# Power_Stage.net
KiCad netlist of a schematic drawn in Altium Designer
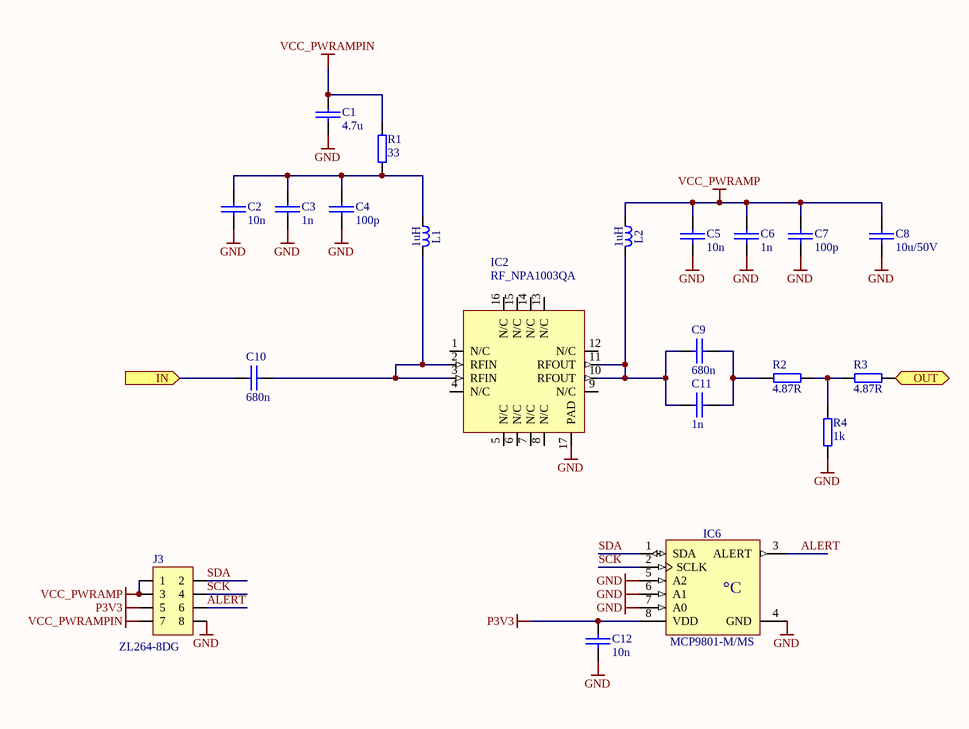
[diagram p0: Power_Stage.SchDoc]

(export (version "E")
  (design (tool "Eeschema 10.0.6"))
  (components
    (comp (ref "C1")
      (value "4.7u")
      (footprint "0603C")
      (description "Capacitor SMD")
      (fields (field (name "PART") "GRM21BR71C475KE51L"))
      (libsource (lib "LIBRARY_SCH") (part "CAP_SMD_0603"))
    )
    (comp (ref "C2")
      (value "10n")
      (footprint "0603C")
      (description "Capacitor SMD")
      (fields (field (name "PART") "GRM1885C1H103JA01D"))
      (libsource (lib "LIBRARY_SCH") (part "CAP_SMD_0603"))
    )
    (comp (ref "C3")
      (value "1n")
      (footprint "0603C")
      (description "Capacitor SMD")
      (fields (field (name "PART") "GRM1885C1H102JA01D"))
      (libsource (lib "LIBRARY_SCH") (part "CAP_SMD_0603"))
    )
    (comp (ref "C4")
      (value "100p")
      (footprint "0603C")
      (description "Capacitor SMD")
      (fields (field (name "PART") "C1608NP01H101J080AA"))
      (libsource (lib "LIBRARY_SCH") (part "CAP_SMD_0603"))
    )
    (comp (ref "C5")
      (value "10n")
      (footprint "0603C")
      (description "Capacitor SMD")
      (fields (field (name "PART") "GRM1885C1H103JA01D"))
      (libsource (lib "LIBRARY_SCH") (part "CAP_SMD_0603"))
    )
    (comp (ref "C6")
      (value "1n")
      (footprint "0603C")
      (description "Capacitor SMD")
      (fields (field (name "PART") "GRM1885C1H102JA01D"))
      (libsource (lib "LIBRARY_SCH") (part "CAP_SMD_0603"))
    )
    (comp (ref "C7")
      (value "100p")
      (footprint "0603C")
      (description "Capacitor SMD")
      (fields (field (name "PART") "C1608NP01H101J080AA"))
      (libsource (lib "LIBRARY_SCH") (part "CAP_SMD_0603"))
    )
    (comp (ref "C8")
      (value "10u/50V")
      (footprint "0805C")
      (description "Capacitor SMD")
      (fields (field (name "PART") "GRM32ER71H106KA12L"))
      (libsource (lib "LIBRARY_SCH") (part "CAP_SMD_0805"))
    )
    (comp (ref "C9")
      (value "680n")
      (footprint "0603C")
      (description "Capacitor SMD")
      (fields (field (name "PART") "GRM1555C1H681GA01"))
      (libsource (lib "LIBRARY_SCH") (part "CAP_SMD_0603"))
    )
    (comp (ref "C10")
      (value "680n")
      (footprint "0603C")
      (description "Capacitor SMD")
      (fields (field (name "PART") "GRM1555C1H681GA01"))
      (libsource (lib "LIBRARY_SCH") (part "CAP_SMD_0603"))
    )
    (comp (ref "C11")
      (value "1n")
      (footprint "0603C")
      (description "Capacitor SMD")
      (fields (field (name "PART") "GRM1885C1H102JA01D"))
      (libsource (lib "LIBRARY_SCH") (part "CAP_SMD_0603"))
    )
    (comp (ref "C12")
      (value "10n")
      (footprint "0603C")
      (description "Capacitor SMD")
      (libsource (lib "LIBRARY_SCH") (part "CAP_SMD_0603"))
    )
    (comp (ref "IC2")
      (value "RF_NPA1003QA")
      (footprint "QFN65P400X400X80_HS-17N")
      (libsource (lib "LIBRARY_SCH") (part "RF_NPA1003QA"))
    )
    (comp (ref "IC6")
      (value "MCP9801-M/MS")
      (footprint "SOP65P490X110-8N")
      (description "2-Wire High-Accuracy Temperature Sensor")
      (fields (field (name "MANUFACTURER") "MICROCHIP TECHNOLOGIY") (field (name "AUTHOR") "CERN DEM JLC"))
      (libsource (lib "ICs And Semiconductors") (part "MCP9801-M/MS"))
    )
    (comp (ref "J3")
      (value "ZL264-8DG")
      (footprint "ZL264-8DG")
      (description "2.54mm pitch connector")
      (libsource (lib "LIBRARY_SCH") (part "CON_2X4 2.54 SMT FEM"))
    )
    (comp (ref "L1")
      (value "1uH")
      (footprint "INDP2520X18L")
      (fields (field (name "PART") "LQW2UAS1R0J00L") (field (name "AUTHOR") "GK"))
      (libsource (lib "LIBRARY_SCH") (part "L_1008_100u"))
    )
    (comp (ref "L2")
      (value "1uH")
      (footprint "INDP2520X18L")
      (description "100uH, 60mA, 21R")
      (fields (field (name "PART") "1008LS-102XJLB") (field (name "AUTHOR") "GK"))
      (libsource (lib "LIBRARY_SCH") (part "L_1008_100u"))
    )
    (comp (ref "R1")
      (value "33")
      (footprint "0603R")
      (description "SMD Resistor")
      (fields (field (name "PART") "CR0603-FX-33R0ELF"))
      (libsource (lib "LIBRARY_SCH") (part "RES_0603"))
    )
    (comp (ref "R2")
      (value "4.87R")
      (footprint "0603R")
      (description "SMD Resistor")
      (fields (field (name "PART") "CPF0603B4R87E1"))
      (libsource (lib "LIBRARY_SCH") (part "RES_0603"))
    )
    (comp (ref "R3")
      (value "4.87R")
      (footprint "0603R")
      (description "SMD Resistor")
      (fields (field (name "PART") "CPF0603B4R87E1"))
      (libsource (lib "LIBRARY_SCH") (part "RES_0603"))
    )
    (comp (ref "R4")
      (value "1k")
      (footprint "0603R")
      (description "SMD Resistor")
      (fields (field (name "PART") "RP73PF1J1K0BTDF"))
      (libsource (lib "LIBRARY_SCH") (part "RES_0603"))
    )
  )
  (nets
    (net (code "1") (name "/ALERT") (class "Default")
      (node (ref "IC6") (pin "3") (pinfunction "ALERT_3") (pintype "output"))
      (node (ref "J3") (pin "6") (pinfunction "6_6") (pintype "passive"))
    )
    (net (code "2") (name "/IN") (class "Default")
      (node (ref "C10") (pin "1") (pinfunction "1_1") (pintype "passive"))
    )
    (net (code "3") (name "/OUT") (class "Default")
      (node (ref "R3") (pin "2") (pinfunction "2_2") (pintype "passive"))
    )
    (net (code "4") (name "/SCK") (class "Default")
      (node (ref "IC6") (pin "2") (pinfunction "SCLK_2") (pintype "input"))
      (node (ref "J3") (pin "4") (pinfunction "4_4") (pintype "passive"))
    )
    (net (code "5") (name "/SDA") (class "Default")
      (node (ref "IC6") (pin "1") (pinfunction "SDA_1") (pintype "bidirectional"))
      (node (ref "J3") (pin "2") (pinfunction "2_2") (pintype "passive"))
    )
    (net (code "6") (name "GND") (class "Default")
      (node (ref "C1") (pin "2") (pinfunction "2_2") (pintype "passive"))
      (node (ref "C12") (pin "1") (pinfunction "1_1") (pintype "passive"))
      (node (ref "C2") (pin "2") (pinfunction "2_2") (pintype "passive"))
      (node (ref "C3") (pin "2") (pinfunction "2_2") (pintype "passive"))
      (node (ref "C4") (pin "2") (pinfunction "2_2") (pintype "passive"))
      (node (ref "C5") (pin "2") (pinfunction "2_2") (pintype "passive"))
      (node (ref "C6") (pin "2") (pinfunction "2_2") (pintype "passive"))
      (node (ref "C7") (pin "2") (pinfunction "2_2") (pintype "passive"))
      (node (ref "C8") (pin "2") (pinfunction "2_2") (pintype "passive"))
      (node (ref "IC2") (pin "17") (pinfunction "PAD_17") (pintype "passive"))
      (node (ref "IC6") (pin "4") (pinfunction "GND_4") (pintype "power_in"))
      (node (ref "IC6") (pin "5") (pinfunction "A2_5") (pintype "input"))
      (node (ref "IC6") (pin "6") (pinfunction "A1_6") (pintype "input"))
      (node (ref "IC6") (pin "7") (pinfunction "A0_7") (pintype "input"))
      (node (ref "J3") (pin "8") (pinfunction "8_8") (pintype "passive"))
      (node (ref "R4") (pin "1") (pinfunction "1_1") (pintype "passive"))
    )
    (net (code "7") (name "Net-(C2-Pad1)") (class "Default")
      (node (ref "C2") (pin "1") (pinfunction "1_1") (pintype "passive"))
      (node (ref "C3") (pin "1") (pinfunction "1_1") (pintype "passive"))
      (node (ref "C4") (pin "1") (pinfunction "1_1") (pintype "passive"))
      (node (ref "L1") (pin "1") (pinfunction "1_1") (pintype "passive"))
      (node (ref "R1") (pin "1") (pinfunction "1_1") (pintype "passive"))
    )
    (net (code "8") (name "Net-(C10-Pad2)") (class "Default")
      (node (ref "C10") (pin "2") (pinfunction "2_2") (pintype "passive"))
      (node (ref "IC2") (pin "2") (pinfunction "RFIN_2") (pintype "input"))
      (node (ref "IC2") (pin "3") (pinfunction "RFIN_3") (pintype "input"))
      (node (ref "L1") (pin "2") (pinfunction "2_2") (pintype "passive"))
    )
    (net (code "9") (name "Net-(C11-Pad1)") (class "Default")
      (node (ref "C11") (pin "1") (pinfunction "1_1") (pintype "passive"))
      (node (ref "C9") (pin "1") (pinfunction "1_1") (pintype "passive"))
      (node (ref "IC2") (pin "10") (pinfunction "RFOUT_10") (pintype "output"))
      (node (ref "IC2") (pin "11") (pinfunction "RFOUT_11") (pintype "output"))
      (node (ref "L2") (pin "2") (pinfunction "2_2") (pintype "passive"))
    )
    (net (code "10") (name "Net-(C11-Pad2)") (class "Default")
      (node (ref "C11") (pin "2") (pinfunction "2_2") (pintype "passive"))
      (node (ref "C9") (pin "2") (pinfunction "2_2") (pintype "passive"))
      (node (ref "R2") (pin "1") (pinfunction "1_1") (pintype "passive"))
    )
    (net (code "11") (name "Net-(R2-Pad2)") (class "Default")
      (node (ref "R2") (pin "2") (pinfunction "2_2") (pintype "passive"))
      (node (ref "R3") (pin "1") (pinfunction "1_1") (pintype "passive"))
      (node (ref "R4") (pin "2") (pinfunction "2_2") (pintype "passive"))
    )
    (net (code "12") (name "P3V3") (class "Default")
      (node (ref "C12") (pin "2") (pinfunction "2_2") (pintype "passive"))
      (node (ref "IC6") (pin "8") (pinfunction "VDD_8") (pintype "power_in"))
      (node (ref "J3") (pin "5") (pinfunction "5_5") (pintype "passive"))
    )
    (net (code "13") (name "VCC_PWRAMP") (class "Default")
      (node (ref "C5") (pin "1") (pinfunction "1_1") (pintype "passive"))
      (node (ref "C6") (pin "1") (pinfunction "1_1") (pintype "passive"))
      (node (ref "C7") (pin "1") (pinfunction "1_1") (pintype "passive"))
      (node (ref "C8") (pin "1") (pinfunction "1_1") (pintype "passive"))
      (node (ref "J3") (pin "1") (pinfunction "1_1") (pintype "passive"))
      (node (ref "J3") (pin "3") (pinfunction "3_3") (pintype "passive"))
      (node (ref "L2") (pin "1") (pinfunction "1_1") (pintype "passive"))
    )
    (net (code "14") (name "VCC_PWRAMPIN") (class "Default")
      (node (ref "C1") (pin "1") (pinfunction "1_1") (pintype "passive"))
      (node (ref "J3") (pin "7") (pinfunction "7_7") (pintype "passive"))
      (node (ref "R1") (pin "2") (pinfunction "2_2") (pintype "passive"))
    )
    (net (code "15") (name "unconnected-(IC2-N{slash}C-Pad1)") (class "Default")
      (node (ref "IC2") (pin "1") (pinfunction "N/C_1") (pintype "passive"))
    )
    (net (code "16") (name "unconnected-(IC2-N{slash}C-Pad4)") (class "Default")
      (node (ref "IC2") (pin "4") (pinfunction "N/C_4") (pintype "passive"))
    )
    (net (code "17") (name "unconnected-(IC2-N{slash}C-Pad5)") (class "Default")
      (node (ref "IC2") (pin "5") (pinfunction "N/C_5") (pintype "passive"))
    )
    (net (code "18") (name "unconnected-(IC2-N{slash}C-Pad6)") (class "Default")
      (node (ref "IC2") (pin "6") (pinfunction "N/C_6") (pintype "passive"))
    )
    (net (code "19") (name "unconnected-(IC2-N{slash}C-Pad7)") (class "Default")
      (node (ref "IC2") (pin "7") (pinfunction "N/C_7") (pintype "passive"))
    )
    (net (code "20") (name "unconnected-(IC2-N{slash}C-Pad8)") (class "Default")
      (node (ref "IC2") (pin "8") (pinfunction "N/C_8") (pintype "passive"))
    )
    (net (code "21") (name "unconnected-(IC2-N{slash}C-Pad9)") (class "Default")
      (node (ref "IC2") (pin "9") (pinfunction "N/C_9") (pintype "passive"))
    )
    (net (code "22") (name "unconnected-(IC2-N{slash}C-Pad12)") (class "Default")
      (node (ref "IC2") (pin "12") (pinfunction "N/C_12") (pintype "passive"))
    )
    (net (code "23") (name "unconnected-(IC2-N{slash}C-Pad13)") (class "Default")
      (node (ref "IC2") (pin "13") (pinfunction "N/C_13") (pintype "passive"))
    )
    (net (code "24") (name "unconnected-(IC2-N{slash}C-Pad14)") (class "Default")
      (node (ref "IC2") (pin "14") (pinfunction "N/C_14") (pintype "passive"))
    )
    (net (code "25") (name "unconnected-(IC2-N{slash}C-Pad15)") (class "Default")
      (node (ref "IC2") (pin "15") (pinfunction "N/C_15") (pintype "passive"))
    )
    (net (code "26") (name "unconnected-(IC2-N{slash}C-Pad16)") (class "Default")
      (node (ref "IC2") (pin "16") (pinfunction "N/C_16") (pintype "passive"))
    )
  )
)
